# SparkFun_LilyPad_Tricolor-LED.net
KiCad netlist of a schematic drawn in EAGLE
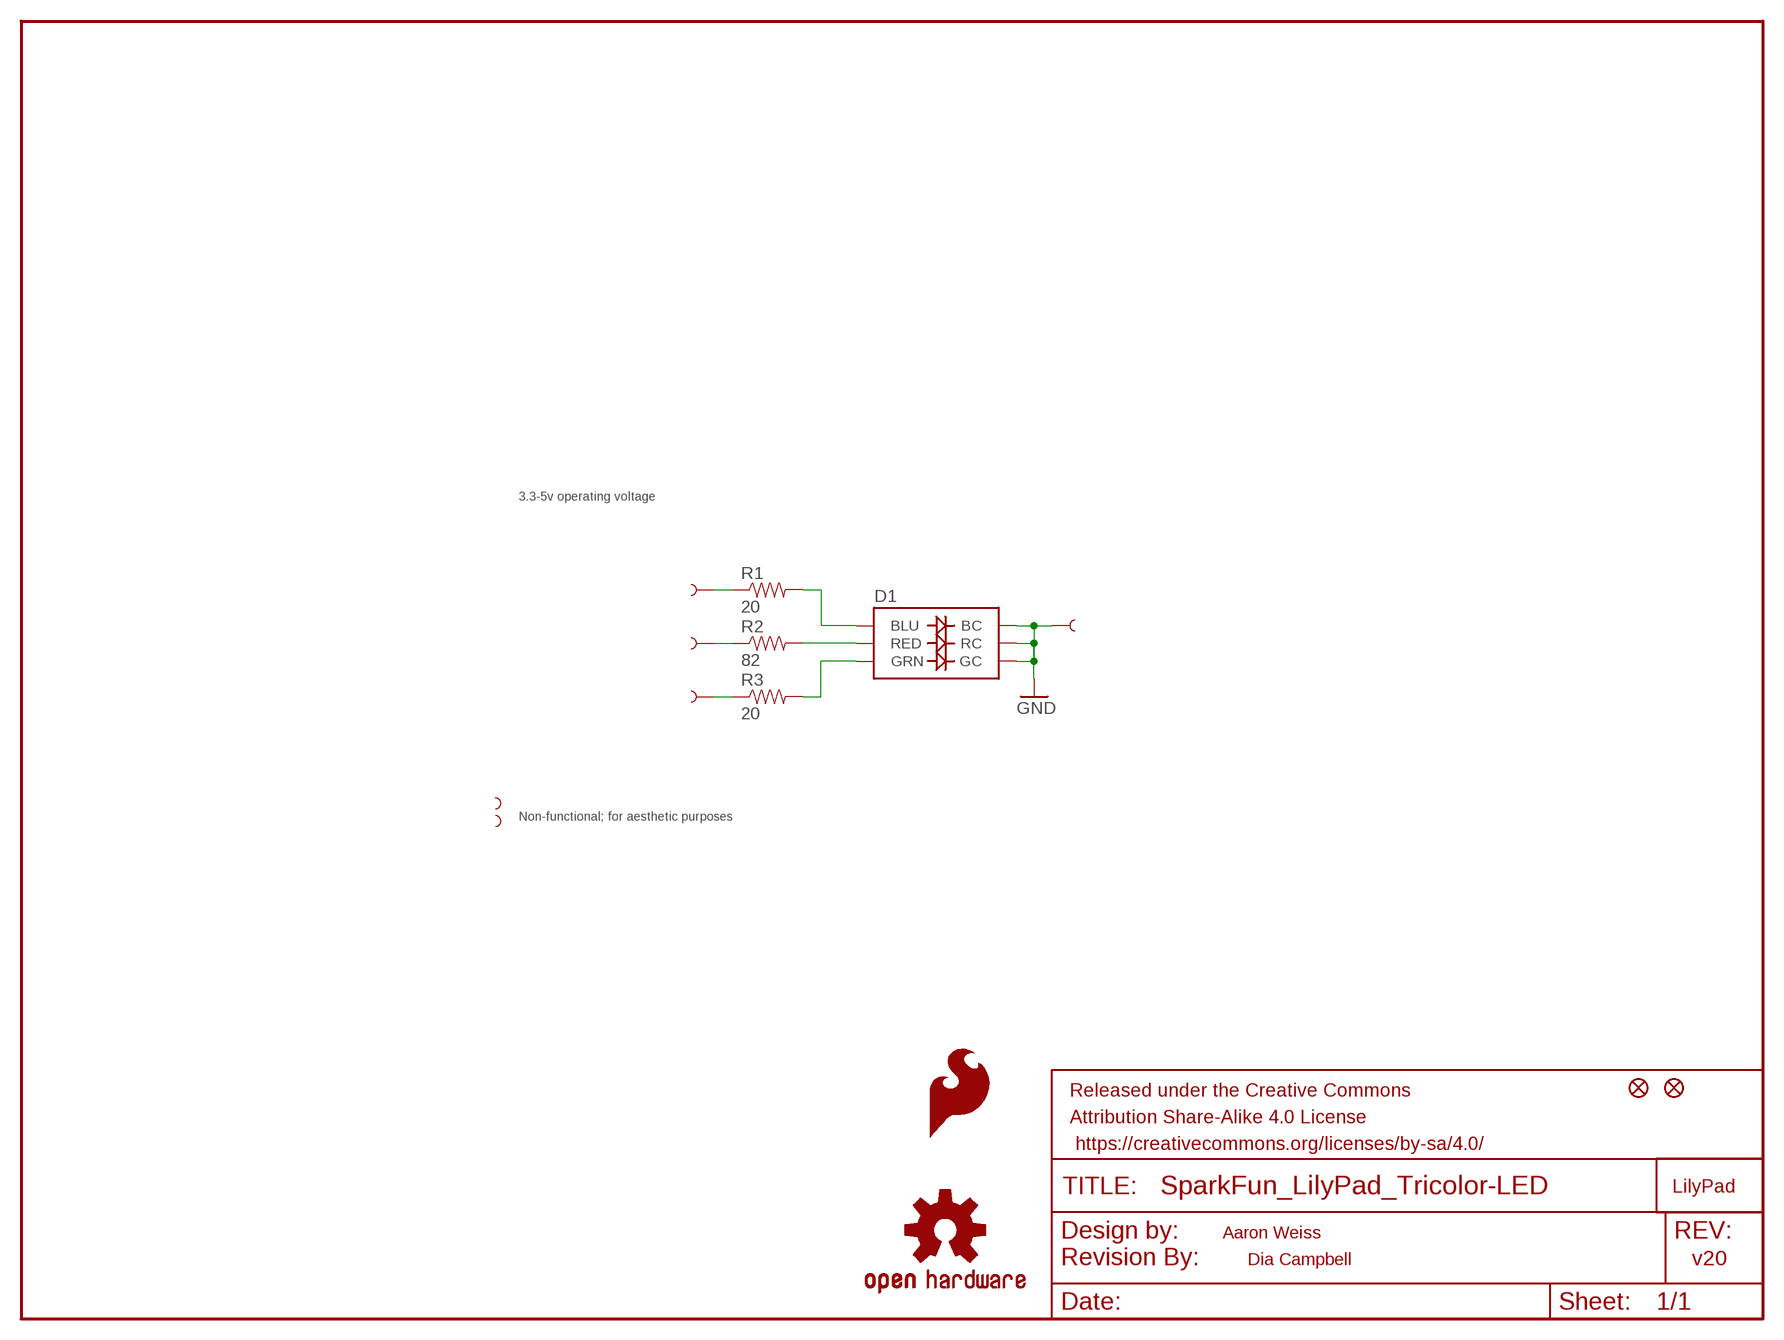
[diagram p0: schematic, sheet 1]

(export (version "E")
  (design (tool "Eeschema 10.0.6"))
  (components
    (comp (ref "BLU")
      (value "SEWTAP6")
      (footprint "eagle-import:PETAL-SMALL-2SIDE")
      (libsource (lib "eagle-import") (part "SEWTAP6"))
    )
    (comp (ref "D1")
      (value "LED-TRICOLOR-NO-COMPLCC-6-SMD")
      (footprint "eagle-import:PLCC-6-LED")
      (libsource (lib "eagle-import") (part "LED-TRICOLOR-NO-COMPLCC-6-SMD"))
    )
    (comp (ref "FID1")
      (value "FIDUCIAL1X2")
      (footprint "eagle-import:FIDUCIAL-1X2")
      (libsource (lib "eagle-import") (part "FIDUCIAL1X2"))
    )
    (comp (ref "FID2")
      (value "FIDUCIAL1X2")
      (footprint "eagle-import:FIDUCIAL-1X2")
      (libsource (lib "eagle-import") (part "FIDUCIAL1X2"))
    )
    (comp (ref "FRAME1")
      (value "FRAME-LETTER")
      (footprint "eagle-import:CREATIVE_COMMONS")
      (fields (field (name "DESIGNER") "NAME"))
      (libsource (lib "eagle-import") (part "FRAME-LETTER"))
    )
    (comp (ref "GND")
      (value "SEWTAP6")
      (footprint "eagle-import:PETAL-SMALL-2SIDE")
      (libsource (lib "eagle-import") (part "SEWTAP6"))
    )
    (comp (ref "GRN")
      (value "SEWTAP6")
      (footprint "eagle-import:PETAL-SMALL-2SIDE")
      (libsource (lib "eagle-import") (part "SEWTAP6"))
    )
    (comp (ref "LOGO1")
      (value "OSHW-LOGOS")
      (footprint "eagle-import:OSHW-LOGO-S")
      (libsource (lib "eagle-import") (part "OSHW-LOGOS"))
    )
    (comp (ref "LOGO2")
      (value "SFE_LOGO_FLAME.1_INCH")
      (footprint "eagle-import:SFE_LOGO_FLAME_.1")
      (libsource (lib "eagle-import") (part "SFE_LOGO_FLAME.1_INCH"))
    )
    (comp (ref "R1")
      (value "20")
      (footprint "eagle-import:0603-RES")
      (libsource (lib "eagle-import") (part "20OHM1/10W1%(0603)SMD"))
    )
    (comp (ref "R2")
      (value "82")
      (footprint "eagle-import:0603-RES")
      (libsource (lib "eagle-import") (part "82OHM-1/10W-1%(0603)SMD"))
    )
    (comp (ref "R3")
      (value "20")
      (footprint "eagle-import:0603-RES")
      (libsource (lib "eagle-import") (part "20OHM1/10W1%(0603)SMD"))
    )
    (comp (ref "RED")
      (value "SEWTAP6")
      (footprint "eagle-import:PETAL-SMALL-2SIDE")
      (libsource (lib "eagle-import") (part "SEWTAP6"))
    )
    (comp (ref "U$1")
      (value "LOGO-LPLP")
      (footprint "eagle-import:LOGO-LILYPAD")
      (libsource (lib "eagle-import") (part "LOGO-LPLP"))
    )
    (comp (ref "U$2")
      (value "SEWTAP-NOHOLE2")
      (footprint "eagle-import:PETAL-NOHOLE-2SIDE")
      (libsource (lib "eagle-import") (part "SEWTAP-NOHOLE2"))
    )
    (comp (ref "U$3")
      (value "SEWTAP-NOHOLE2")
      (footprint "eagle-import:PETAL-NOHOLE-2SIDE")
      (libsource (lib "eagle-import") (part "SEWTAP-NOHOLE2"))
    )
    (comp (ref "U$4")
      (value "REVISION")
      (footprint "eagle-import:REVISION")
      (libsource (lib "eagle-import") (part "REVISION"))
    )
  )
  (nets
    (net (code "1") (name "GND") (class "Default")
      (node (ref "D1") (pin "CB") (pinfunction "BC_CB") (pintype "bidirectional"))
      (node (ref "D1") (pin "CG") (pinfunction "GC_CG") (pintype "bidirectional"))
      (node (ref "D1") (pin "CR") (pinfunction "RC_CR") (pintype "bidirectional"))
      (node (ref "GND") (pin "1") (pinfunction "1_1") (pintype "bidirectional"))
    )
    (net (code "2") (name "Net-(BLU-Pad1)") (class "Default")
      (node (ref "BLU") (pin "1") (pinfunction "1_1") (pintype "bidirectional"))
      (node (ref "R1") (pin "1") (pinfunction "1_1") (pintype "passive"))
    )
    (net (code "3") (name "Net-(D1-BLU)") (class "Default")
      (node (ref "D1") (pin "AB") (pinfunction "BLU_AB") (pintype "bidirectional"))
      (node (ref "R1") (pin "2") (pinfunction "2_2") (pintype "passive"))
    )
    (net (code "4") (name "Net-(D1-GRN)") (class "Default")
      (node (ref "D1") (pin "AG") (pinfunction "GRN_AG") (pintype "bidirectional"))
      (node (ref "R3") (pin "2") (pinfunction "2_2") (pintype "passive"))
    )
    (net (code "5") (name "Net-(D1-RED)") (class "Default")
      (node (ref "D1") (pin "AR") (pinfunction "RED_AR") (pintype "bidirectional"))
      (node (ref "R2") (pin "2") (pinfunction "2_2") (pintype "passive"))
    )
    (net (code "6") (name "Net-(GRN-Pad1)") (class "Default")
      (node (ref "GRN") (pin "1") (pinfunction "1_1") (pintype "bidirectional"))
      (node (ref "R3") (pin "1") (pinfunction "1_1") (pintype "passive"))
    )
    (net (code "7") (name "Net-(R2-Pad1)") (class "Default")
      (node (ref "R2") (pin "1") (pinfunction "1_1") (pintype "passive"))
      (node (ref "RED") (pin "1") (pinfunction "1_1") (pintype "bidirectional"))
    )
  )
)
